# p5_ethernet.net
KiCad netlist of a schematic drawn in Altium Designer
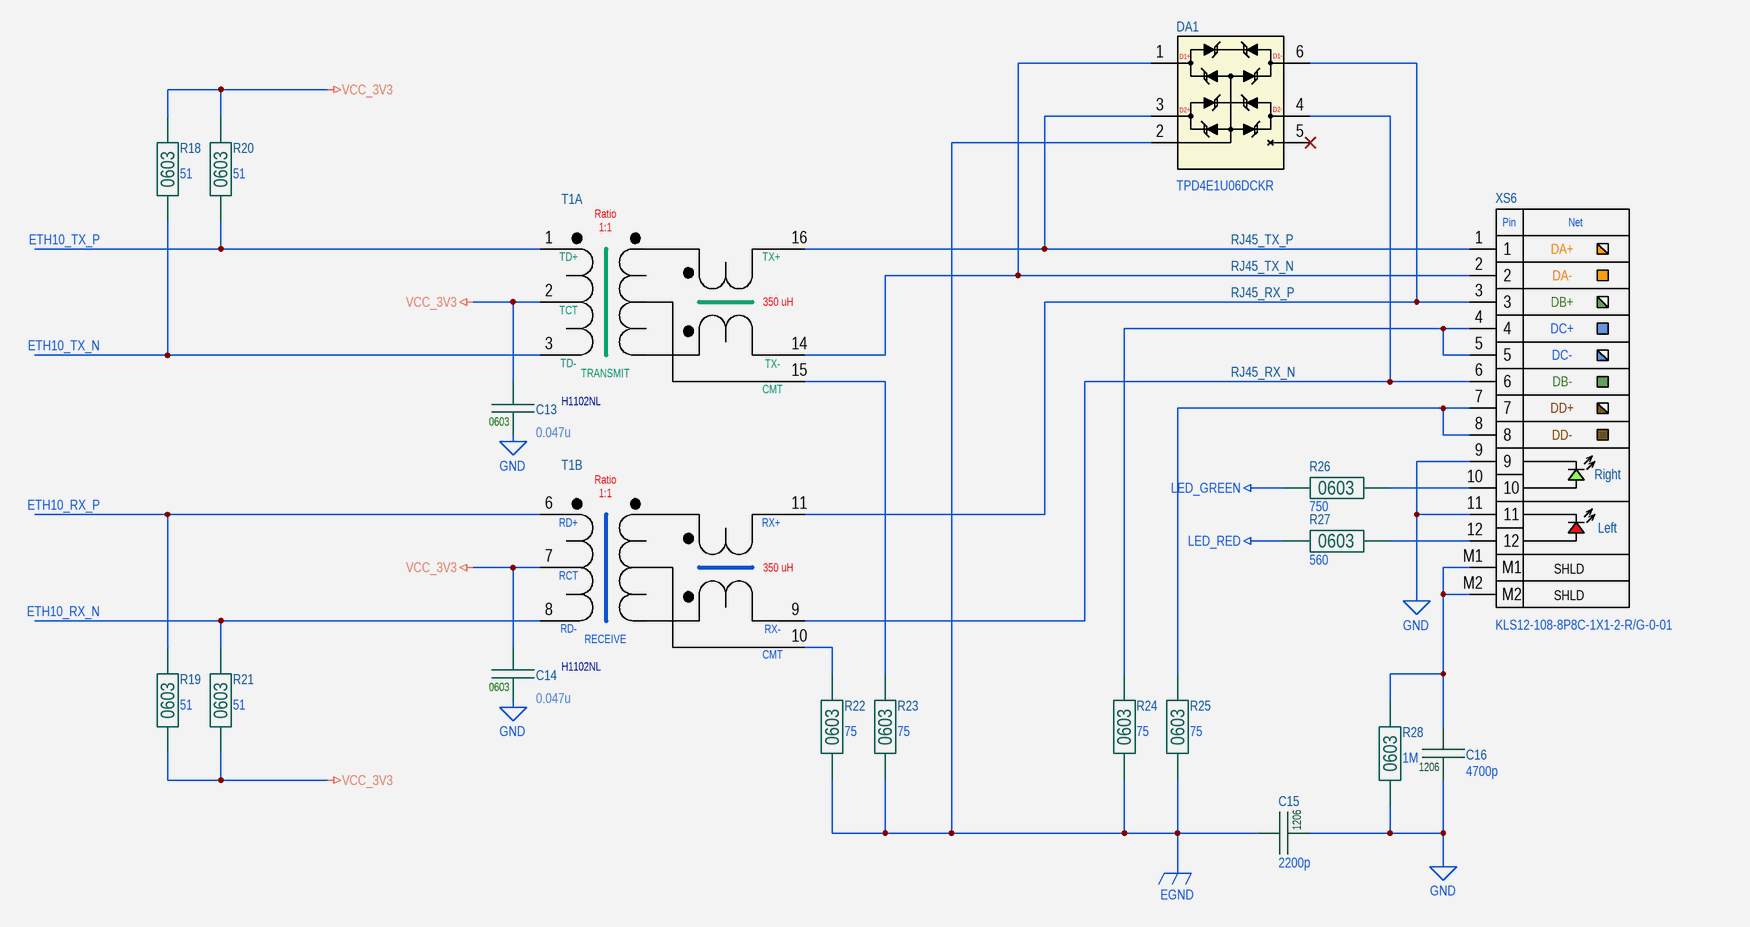
[diagram p0: p5_ethernet.SchDoc]

(export (version "E")
  (design (tool "Eeschema 10.0.6"))
  (components
    (comp (ref "C13")
      (value "0.047u")
      (footprint "PcbLib_RC:CAP0603")
      (description "Capacitors 0603 package case")
      (fields
        (field (name "TOLERANCE") "± 10 %")
        (field (name "VOLTAGE") "50V")
        (field (name "PACKAGE") "0603")
      )
      (libsource (lib "Schlib_RC") (part "C0603"))
    )
    (comp (ref "C14")
      (value "0.047u")
      (footprint "PcbLib_RC:CAP0603")
      (description "Capacitors 0603 package case")
      (fields
        (field (name "TOLERANCE") "± 10 %")
        (field (name "VOLTAGE") "50V")
        (field (name "PACKAGE") "0603")
      )
      (libsource (lib "Schlib_RC") (part "C0603"))
    )
    (comp (ref "C15")
      (value "2200p")
      (footprint "PcbLib_RC:CAP1206-1.0")
      (description "Capacitors 1206 package case")
      (fields
        (field (name "TOLERANCE") "± 10 %")
        (field (name "VOLTAGE") "1000V")
        (field (name "PACKAGE") "1206")
      )
      (libsource (lib "Schlib_RC") (part "C1206"))
    )
    (comp (ref "C16")
      (value "4700p")
      (footprint "PcbLib_RC:CAP1206-1.4")
      (description "Capacitors 1206 package case")
      (fields
        (field (name "TOLERANCE") "± 10 %")
        (field (name "VOLTAGE") "1000V")
        (field (name "PACKAGE") "1206")
      )
      (libsource (lib "Schlib_RC") (part "C1206"))
    )
    (comp (ref "DA1")
      (value "TPD4E1U06DCKR")
      (footprint "PcbLib_ICs:SC70-6")
      (description "6 Quad-Channel, High-Speed ESD Protection Device")
      (fields (field (name "MANUFACTURER") "Texas Instruments"))
      (libsource (lib "Schlib_Texas_Instruments") (part "TPD4E1U06DCKR"))
    )
    (comp (ref "R18")
      (value "51")
      (footprint "PcbLib_RC:RES0603B")
      (description "Resistor 0603 package case")
      (fields
        (field (name "TOLERANCE") "± 1 %")
        (field (name "PART NUMBER") "RC0603FR-0751RL")
        (field (name "PACKAGE") "0603")
      )
      (libsource (lib "Schlib_RC") (part "R0603"))
    )
    (comp (ref "R19")
      (value "51")
      (footprint "PcbLib_RC:RES0603B")
      (description "Resistor 0603 package case")
      (fields
        (field (name "TOLERANCE") "± 1 %")
        (field (name "PART NUMBER") "RC0603FR-0751RL")
        (field (name "PACKAGE") "0603")
      )
      (libsource (lib "Schlib_RC") (part "R0603"))
    )
    (comp (ref "R20")
      (value "51")
      (footprint "PcbLib_RC:RES0603B")
      (description "Resistor 0603 package case")
      (fields
        (field (name "TOLERANCE") "± 1 %")
        (field (name "PART NUMBER") "RC0603FR-0751RL")
        (field (name "PACKAGE") "0603")
      )
      (libsource (lib "Schlib_RC") (part "R0603"))
    )
    (comp (ref "R21")
      (value "51")
      (footprint "PcbLib_RC:RES0603B")
      (description "Resistor 0603 package case")
      (fields
        (field (name "TOLERANCE") "± 1 %")
        (field (name "PART NUMBER") "RC0603FR-0751RL")
        (field (name "PACKAGE") "0603")
      )
      (libsource (lib "Schlib_RC") (part "R0603"))
    )
    (comp (ref "R22")
      (value "75")
      (footprint "PcbLib_RC:RES0603B")
      (description "Resistor 0603 package case")
      (fields
        (field (name "TOLERANCE") "± 1 %")
        (field (name "PART NUMBER") "RC0603FR-0775RL")
        (field (name "PACKAGE") "0603")
      )
      (libsource (lib "Schlib_RC") (part "R0603"))
    )
    (comp (ref "R23")
      (value "75")
      (footprint "PcbLib_RC:RES0603B")
      (description "Resistor 0603 package case")
      (fields
        (field (name "TOLERANCE") "± 1 %")
        (field (name "PART NUMBER") "RC0603FR-0775RL")
        (field (name "PACKAGE") "0603")
      )
      (libsource (lib "Schlib_RC") (part "R0603"))
    )
    (comp (ref "R24")
      (value "75")
      (footprint "PcbLib_RC:RES0603B")
      (description "Resistor 0603 package case")
      (fields
        (field (name "TOLERANCE") "± 1 %")
        (field (name "PART NUMBER") "RC0603FR-0775RL")
        (field (name "PACKAGE") "0603")
      )
      (libsource (lib "Schlib_RC") (part "R0603"))
    )
    (comp (ref "R25")
      (value "75")
      (footprint "PcbLib_RC:RES0603B")
      (description "Resistor 0603 package case")
      (fields
        (field (name "TOLERANCE") "± 1 %")
        (field (name "PART NUMBER") "RC0603FR-0775RL")
        (field (name "PACKAGE") "0603")
      )
      (libsource (lib "Schlib_RC") (part "R0603"))
    )
    (comp (ref "R26")
      (value "750")
      (footprint "PcbLib_RC:RES0603B")
      (description "Resistor 0603 package case")
      (fields
        (field (name "TOLERANCE") "± 1 %")
        (field (name "PART NUMBER") "RC0603FR-07750RL")
        (field (name "PACKAGE") "0603")
      )
      (libsource (lib "Schlib_RC") (part "R0603"))
    )
    (comp (ref "R27")
      (value "560")
      (footprint "PcbLib_RC:RES0603B")
      (description "Resistor 0603 package case")
      (fields
        (field (name "TOLERANCE") "± 1 %")
        (field (name "PART NUMBER") "RC0603FR-07560RL")
        (field (name "PACKAGE") "0603")
      )
      (libsource (lib "Schlib_RC") (part "R0603"))
    )
    (comp (ref "R28")
      (value "1M")
      (footprint "PcbLib_RC:RES0603B")
      (description "Resistor 0603 package case")
      (fields
        (field (name "TOLERANCE") "± 1 %")
        (field (name "PART NUMBER") "RC0603FR-071ML")
        (field (name "PACKAGE") "0603")
      )
      (libsource (lib "Schlib_RC") (part "R0603"))
    )
    (comp (ref "T1")
      (value "H1102NL")
      (footprint "PcbLib_Others:H1102NL")
      (description "10/100BASE-T Ethernet transformer Ratio 1:1 350 uH")
      (fields (field (name "MANUFACTURER") "Pulse Electronics"))
      (libsource (lib "Schlib_Pulse_Electronics") (part "H1102NL"))
    )
    (comp (ref "XS6")
      (value "KLS12-108-8P8C-1X1-2-R/G-0-01")
      (footprint "PcbLib_Connectors:L-KLS12-108-8P8C_SLOTS")
      (description "RJ-45")
      (fields (field (name "MANUFACTURER") "KLS") (field (name "AUTHOR") "Sklyarov"))
      (libsource (lib "Schlib_KLS") (part "KLS12-108-8P8C-1X1-2-R/G-0-01"))
    )
  )
  (nets
    (net (code "1") (name "/ETH10_RX_N") (class "Default")
      (node (ref "R21") (pin "2") (pinfunction "2_2") (pintype "passive"))
      (node (ref "T1") (pin "8") (pinfunction "RD-_8") (pintype "passive"))
    )
    (net (code "2") (name "/ETH10_RX_P") (class "Default")
      (node (ref "R19") (pin "2") (pinfunction "2_2") (pintype "passive"))
      (node (ref "T1") (pin "6") (pinfunction "RD+_6") (pintype "passive"))
    )
    (net (code "3") (name "/ETH10_TX_N") (class "Default")
      (node (ref "R18") (pin "1") (pinfunction "1_1") (pintype "passive"))
      (node (ref "T1") (pin "3") (pinfunction "TD-_3") (pintype "passive"))
    )
    (net (code "4") (name "/ETH10_TX_P") (class "Default")
      (node (ref "R20") (pin "1") (pinfunction "1_1") (pintype "passive"))
      (node (ref "T1") (pin "1") (pinfunction "TD+_1") (pintype "passive"))
    )
    (net (code "5") (name "/RJ45_RX_N") (class "Default")
      (node (ref "DA1") (pin "4") (pinfunction "D2-_4") (pintype "passive"))
      (node (ref "T1") (pin "9") (pinfunction "RX-_9") (pintype "passive"))
      (node (ref "XS6") (pin "6") (pinfunction "6_6") (pintype "passive"))
    )
    (net (code "6") (name "/RJ45_RX_P") (class "Default")
      (node (ref "DA1") (pin "6") (pinfunction "D1-_6") (pintype "passive"))
      (node (ref "T1") (pin "11") (pinfunction "RX+_11") (pintype "passive"))
      (node (ref "XS6") (pin "3") (pinfunction "3_3") (pintype "passive"))
    )
    (net (code "7") (name "/RJ45_TX_N") (class "Default")
      (node (ref "DA1") (pin "1") (pinfunction "D1+_1") (pintype "passive"))
      (node (ref "T1") (pin "14") (pinfunction "TX-_14") (pintype "passive"))
      (node (ref "XS6") (pin "2") (pinfunction "2_2") (pintype "passive"))
    )
    (net (code "8") (name "/RJ45_TX_P") (class "Default")
      (node (ref "DA1") (pin "3") (pinfunction "D2+_3") (pintype "passive"))
      (node (ref "T1") (pin "16") (pinfunction "TX+_16") (pintype "passive"))
      (node (ref "XS6") (pin "1") (pinfunction "1_1") (pintype "passive"))
    )
    (net (code "9") (name "EGND") (class "Default")
      (node (ref "C15") (pin "1") (pinfunction "1_1") (pintype "passive"))
      (node (ref "DA1") (pin "2") (pinfunction "GND_2") (pintype "power_in"))
      (node (ref "R22") (pin "1") (pinfunction "1_1") (pintype "passive"))
      (node (ref "R23") (pin "1") (pinfunction "1_1") (pintype "passive"))
      (node (ref "R24") (pin "1") (pinfunction "1_1") (pintype "passive"))
      (node (ref "R25") (pin "1") (pinfunction "1_1") (pintype "passive"))
    )
    (net (code "10") (name "GND") (class "Default")
      (node (ref "C13") (pin "1") (pinfunction "1_1") (pintype "passive"))
      (node (ref "C14") (pin "1") (pinfunction "1_1") (pintype "passive"))
      (node (ref "C15") (pin "2") (pinfunction "2_2") (pintype "passive"))
      (node (ref "C16") (pin "1") (pinfunction "1_1") (pintype "passive"))
      (node (ref "R28") (pin "1") (pinfunction "1_1") (pintype "passive"))
      (node (ref "XS6") (pin "11") (pinfunction "11_11") (pintype "passive"))
      (node (ref "XS6") (pin "9") (pinfunction "9_9") (pintype "passive"))
    )
    (net (code "11") (name "LED_GREEN") (class "Default")
      (node (ref "R26") (pin "2") (pinfunction "2_2") (pintype "passive"))
    )
    (net (code "12") (name "LED_RED") (class "Default")
      (node (ref "R27") (pin "2") (pinfunction "2_2") (pintype "passive"))
    )
    (net (code "13") (name "Net-(C16-Pad2)") (class "Default")
      (node (ref "C16") (pin "2") (pinfunction "2_2") (pintype "passive"))
      (node (ref "R28") (pin "2") (pinfunction "2_2") (pintype "passive"))
      (node (ref "XS6") (pin "M1") (pinfunction "M1_M1") (pintype "passive"))
      (node (ref "XS6") (pin "M2") (pinfunction "M2_M2") (pintype "passive"))
    )
    (net (code "14") (name "Net-(R24-Pad2)") (class "Default")
      (node (ref "R24") (pin "2") (pinfunction "2_2") (pintype "passive"))
      (node (ref "XS6") (pin "4") (pinfunction "4_4") (pintype "passive"))
      (node (ref "XS6") (pin "5") (pinfunction "5_5") (pintype "passive"))
    )
    (net (code "15") (name "Net-(R25-Pad2)") (class "Default")
      (node (ref "R25") (pin "2") (pinfunction "2_2") (pintype "passive"))
      (node (ref "XS6") (pin "7") (pinfunction "7_7") (pintype "passive"))
      (node (ref "XS6") (pin "8") (pinfunction "8_8") (pintype "passive"))
    )
    (net (code "16") (name "Net-(R26-Pad1)") (class "Default")
      (node (ref "R26") (pin "1") (pinfunction "1_1") (pintype "passive"))
      (node (ref "XS6") (pin "10") (pinfunction "10_10") (pintype "passive"))
    )
    (net (code "17") (name "Net-(R27-Pad1)") (class "Default")
      (node (ref "R27") (pin "1") (pinfunction "1_1") (pintype "passive"))
      (node (ref "XS6") (pin "12") (pinfunction "12_12") (pintype "passive"))
    )
    (net (code "18") (name "Net-(T1A-CMTT)") (class "Default")
      (node (ref "R23") (pin "2") (pinfunction "2_2") (pintype "passive"))
      (node (ref "T1") (pin "15") (pinfunction "CMTT_15") (pintype "passive"))
    )
    (net (code "19") (name "Net-(T1B-CMTR)") (class "Default")
      (node (ref "R22") (pin "2") (pinfunction "2_2") (pintype "passive"))
      (node (ref "T1") (pin "10") (pinfunction "CMTR_10") (pintype "passive"))
    )
    (net (code "20") (name "VCC_3V3") (class "Default")
      (node (ref "C13") (pin "2") (pinfunction "2_2") (pintype "passive"))
      (node (ref "C14") (pin "2") (pinfunction "2_2") (pintype "passive"))
      (node (ref "R18") (pin "2") (pinfunction "2_2") (pintype "passive"))
      (node (ref "R19") (pin "1") (pinfunction "1_1") (pintype "passive"))
      (node (ref "R20") (pin "2") (pinfunction "2_2") (pintype "passive"))
      (node (ref "R21") (pin "1") (pinfunction "1_1") (pintype "passive"))
      (node (ref "T1") (pin "2") (pinfunction "TCT_2") (pintype "passive"))
      (node (ref "T1") (pin "7") (pinfunction "RCT_7") (pintype "passive"))
    )
    (net (code "21") (name "unconnected-(DA1-NC-Pad5)") (class "Default")
      (node (ref "DA1") (pin "5") (pinfunction "NC_5") (pintype "tri_state+no_connect"))
    )
  )
)
